# Receptor.net
KiCad netlist of a schematic drawn in Altium Designer
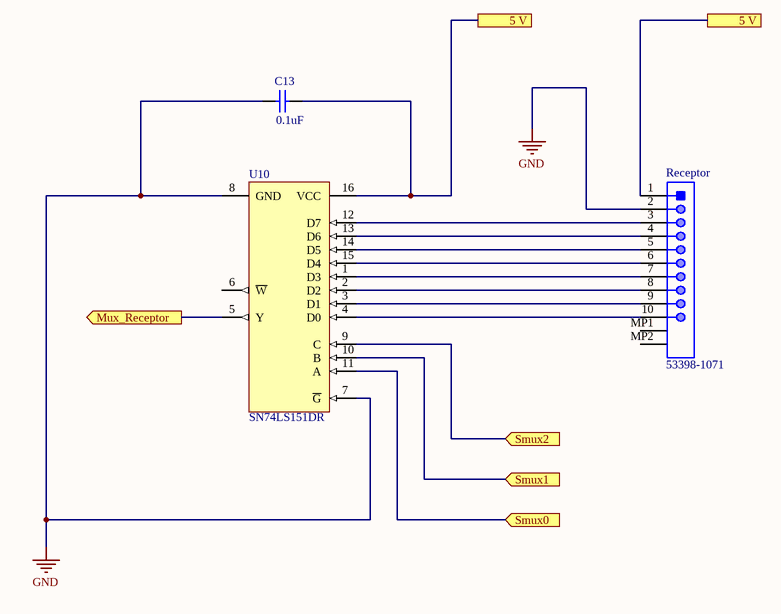
[diagram p0: Receptor.SchDoc]

(export (version "E")
  (design (tool "Eeschema 10.0.6"))
  (components
    (comp (ref "C13")
      (value "710-885012206071")
      (footprint "CAPC1608X90X30LL10T20")
      (fields
        (field (name "VOLTAGE") "25Vdc")
        (field (name "MANUFACTURER") "SamsungElectro-Mechanics")
        (field (name "CAPACITANCE VALUE") "0.1uF")
        (field (name "TOLERANCE") "10%")
      )
      (libsource (lib "CAP 0603 100nF") (part "CMP-2000-06092-1"))
    )
    (comp (ref "Receptor")
      (value "53398-1071")
      (footprint "MOLX-53398-1071_V")
      (description "Male Header, Pitch 1.25 mm, 1 x 10 Position, Height 4.7 mm, -40 to 85 degC, RoHS, Tape and Reel")
      (fields (field (name "MANUFACTURER") "Molex"))
      (libsource (lib "Molex_53398-1071") (part "CMP-2000-05635-1"))
    )
    (comp (ref "U10")
      (value "SN74LS151DR")
      (footprint "D0016A_L")
      (description "8-Line To 1-Line Data Selectors/Multiplexers, D0016A, LARGE T&R")
      (fields
        (field (name "MANUFACTURER") "Texas Instruments")
        (field (name "GENERIC PART NUMBER") "SN74LS151")
      )
      (libsource (lib "mux SN74LS151DR") (part "CMP-1633-00148-1"))
    )
  )
  (nets
    (net (code "1") (name "/5 V") (class "Default")
      (node (ref "C13") (pin "2") (pinfunction "2_2") (pintype "passive"))
      (node (ref "Receptor") (pin "1") (pinfunction "1_1") (pintype "passive"))
      (node (ref "U10") (pin "16") (pinfunction "VCC_16") (pintype "power_in"))
    )
    (net (code "2") (name "/Mux_Receptor") (class "Default")
      (node (ref "U10") (pin "5") (pinfunction "Y_5") (pintype "output"))
    )
    (net (code "3") (name "/Smux0") (class "Default")
      (node (ref "U10") (pin "11") (pinfunction "A_11") (pintype "input"))
    )
    (net (code "4") (name "/Smux1") (class "Default")
      (node (ref "U10") (pin "10") (pinfunction "B_10") (pintype "input"))
    )
    (net (code "5") (name "/Smux2") (class "Default")
      (node (ref "U10") (pin "9") (pinfunction "C_9") (pintype "input"))
    )
    (net (code "6") (name "GND") (class "Default")
      (node (ref "C13") (pin "1") (pinfunction "1_1") (pintype "passive"))
      (node (ref "Receptor") (pin "2") (pinfunction "2_2") (pintype "passive"))
      (node (ref "U10") (pin "7") (pinfunction "~{G}_7") (pintype "input"))
      (node (ref "U10") (pin "8") (pinfunction "GND_8") (pintype "power_in"))
    )
    (net (code "7") (name "Net-(U10-D0)") (class "Default")
      (node (ref "Receptor") (pin "10") (pinfunction "10_10") (pintype "passive"))
      (node (ref "U10") (pin "4") (pinfunction "D0_4") (pintype "input"))
    )
    (net (code "8") (name "Net-(U10-D1)") (class "Default")
      (node (ref "Receptor") (pin "9") (pinfunction "9_9") (pintype "passive"))
      (node (ref "U10") (pin "3") (pinfunction "D1_3") (pintype "input"))
    )
    (net (code "9") (name "Net-(U10-D2)") (class "Default")
      (node (ref "Receptor") (pin "8") (pinfunction "8_8") (pintype "passive"))
      (node (ref "U10") (pin "2") (pinfunction "D2_2") (pintype "input"))
    )
    (net (code "10") (name "Net-(U10-D3)") (class "Default")
      (node (ref "Receptor") (pin "7") (pinfunction "7_7") (pintype "passive"))
      (node (ref "U10") (pin "1") (pinfunction "D3_1") (pintype "input"))
    )
    (net (code "11") (name "Net-(U10-D4)") (class "Default")
      (node (ref "Receptor") (pin "6") (pinfunction "6_6") (pintype "passive"))
      (node (ref "U10") (pin "15") (pinfunction "D4_15") (pintype "input"))
    )
    (net (code "12") (name "Net-(U10-D5)") (class "Default")
      (node (ref "Receptor") (pin "5") (pinfunction "5_5") (pintype "passive"))
      (node (ref "U10") (pin "14") (pinfunction "D5_14") (pintype "input"))
    )
    (net (code "13") (name "Net-(U10-D6)") (class "Default")
      (node (ref "Receptor") (pin "4") (pinfunction "4_4") (pintype "passive"))
      (node (ref "U10") (pin "13") (pinfunction "D6_13") (pintype "input"))
    )
    (net (code "14") (name "Net-(U10-D7)") (class "Default")
      (node (ref "Receptor") (pin "3") (pinfunction "3_3") (pintype "passive"))
      (node (ref "U10") (pin "12") (pinfunction "D7_12") (pintype "input"))
    )
    (net (code "15") (name "unconnected-(Receptor-PadMP1)") (class "Default")
      (node (ref "Receptor") (pin "MP1") (pinfunction "MP1_MP1") (pintype "passive"))
    )
    (net (code "16") (name "unconnected-(Receptor-PadMP2)") (class "Default")
      (node (ref "Receptor") (pin "MP2") (pinfunction "MP2_MP2") (pintype "passive"))
    )
    (net (code "17") (name "unconnected-(U10-~{W}-Pad6)") (class "Default")
      (node (ref "U10") (pin "6") (pinfunction "~{W}_6") (pintype "output"))
    )
  )
)
